# Codeshelf-0005_v02.net
KiCad netlist of a schematic drawn in EAGLE
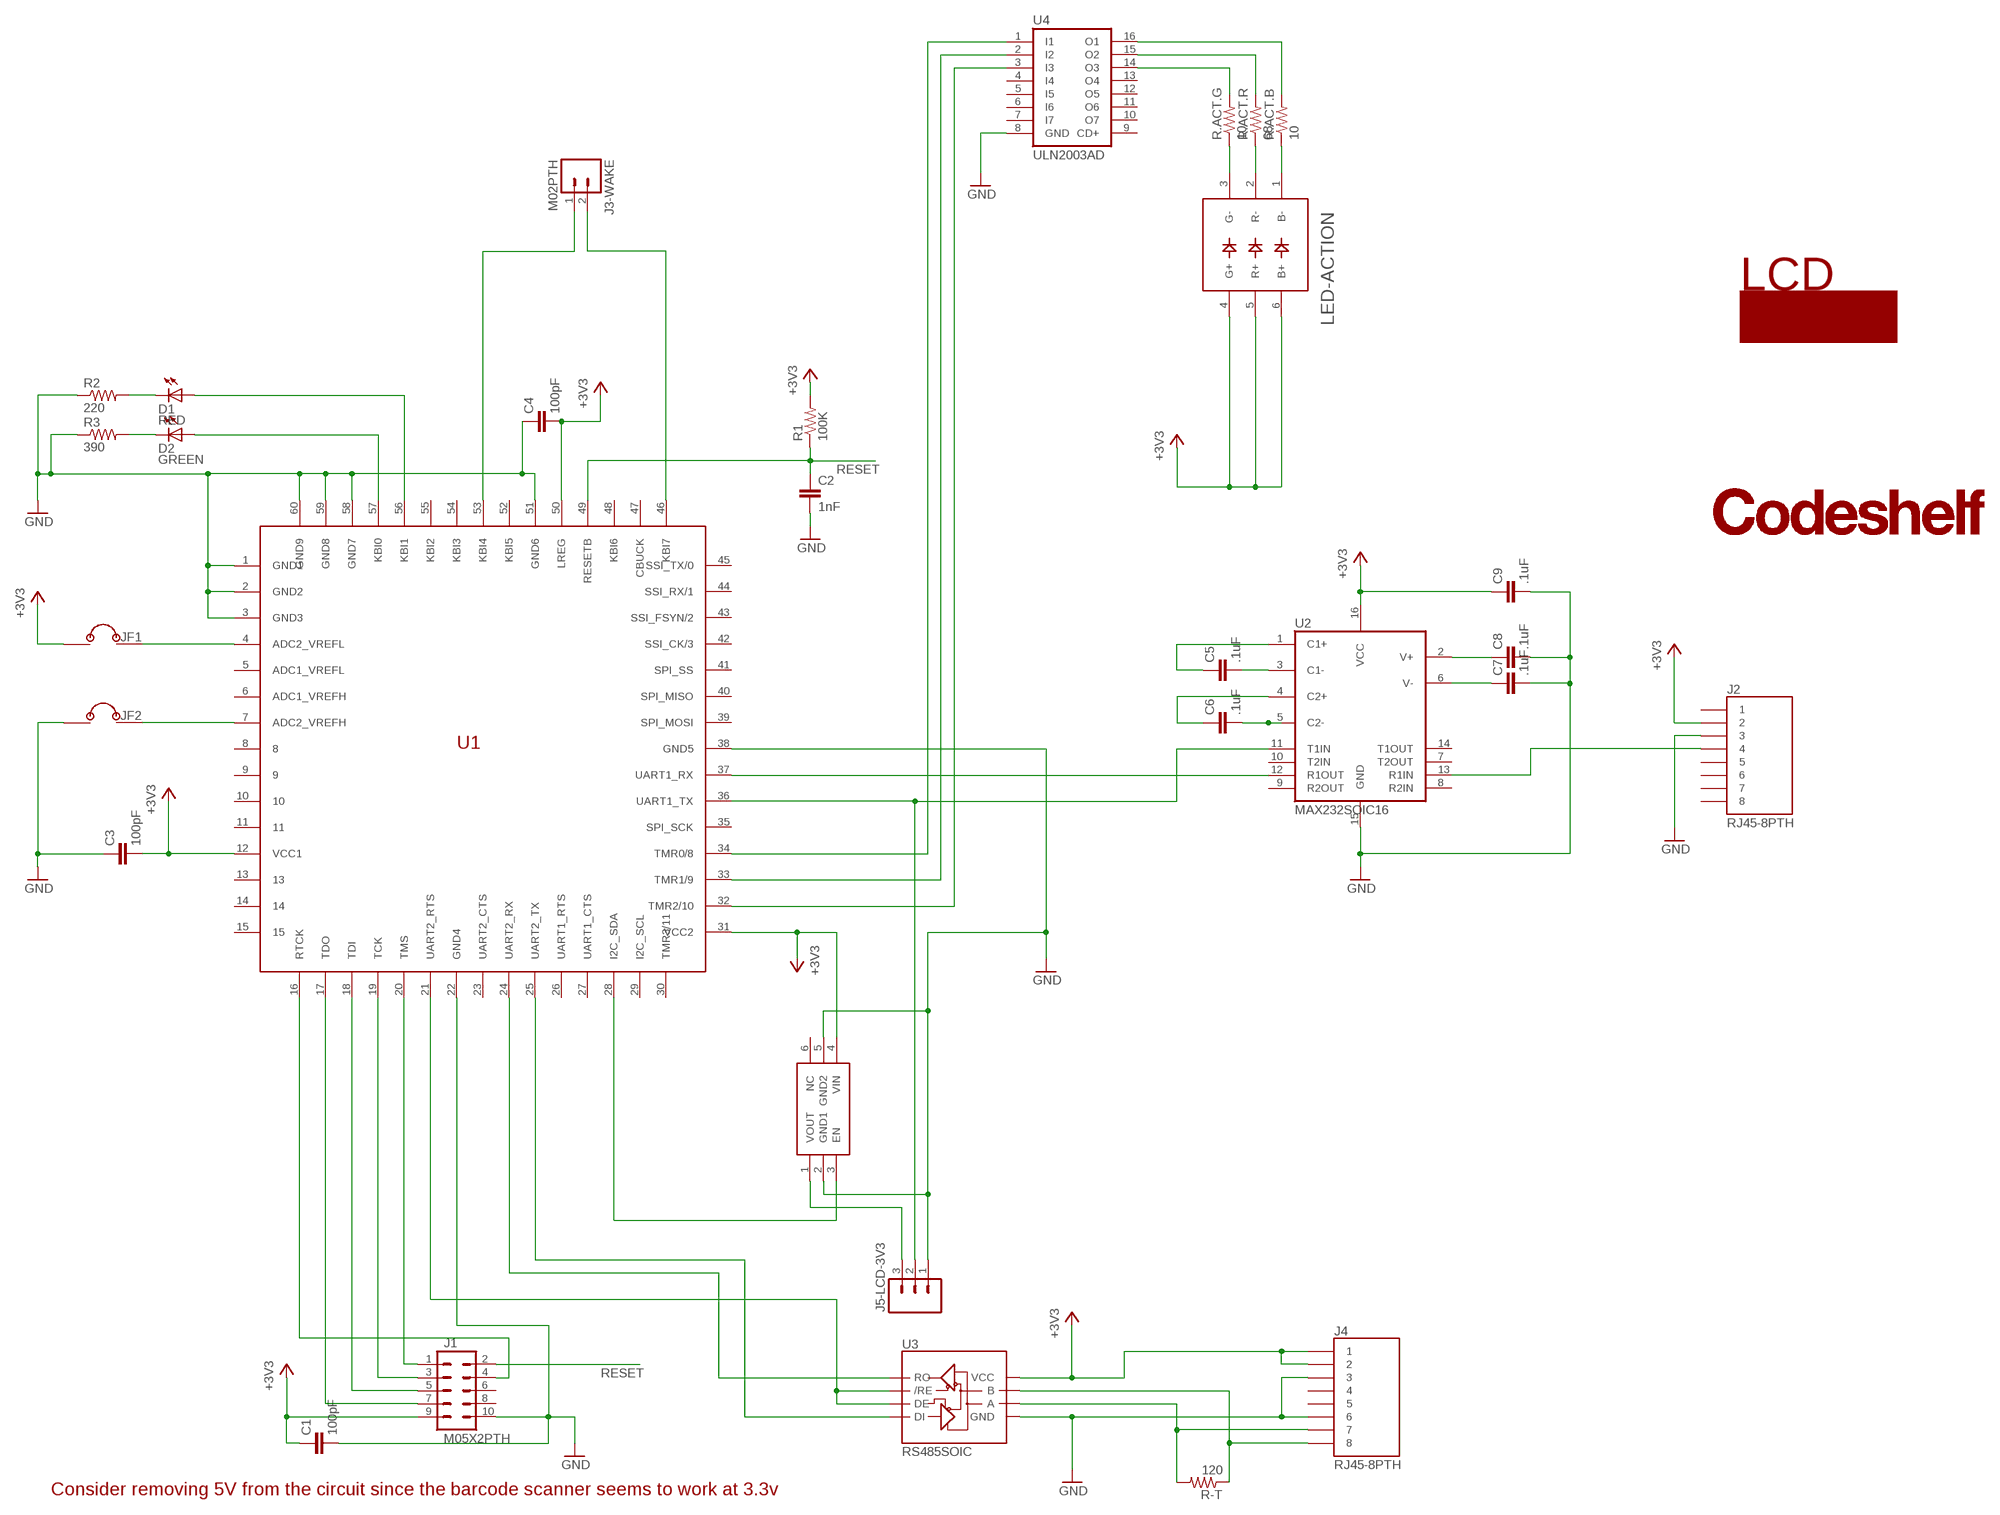
[diagram p0: schematic, sheet 1]
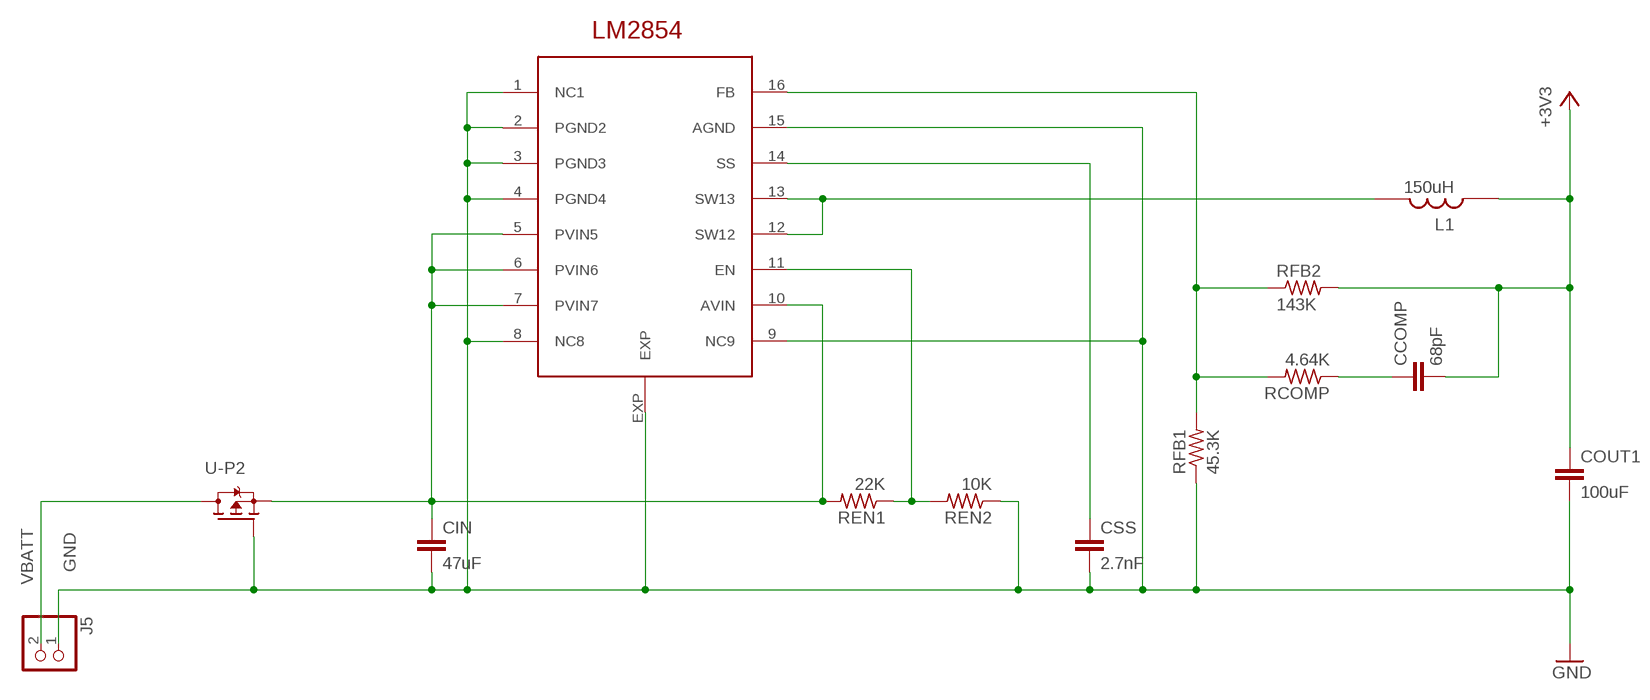
[diagram p1: schematic, sheet 2]

(export (version "E")
  (design (tool "Eeschema 10.0.6"))
  (components
    (comp (ref "C1")
      (value "100pF")
      (footprint "eagle-import:C0603")
      (libsource (lib "eagle-import") (part "RF-C0603"))
    )
    (comp (ref "C2")
      (value "1nF")
      (footprint "eagle-import:C0603")
      (libsource (lib "eagle-import") (part "RF-C0603"))
    )
    (comp (ref "C3")
      (value "100pF")
      (footprint "eagle-import:C0603")
      (libsource (lib "eagle-import") (part "RF-C0603"))
    )
    (comp (ref "C4")
      (value "100pF")
      (footprint "eagle-import:C0603")
      (libsource (lib "eagle-import") (part "RF-C0603"))
    )
    (comp (ref "C5")
      (value ".1uF")
      (footprint "eagle-import:C0402")
      (libsource (lib "eagle-import") (part "RF-C0402"))
    )
    (comp (ref "C6")
      (value ".1uF")
      (footprint "eagle-import:C0402")
      (libsource (lib "eagle-import") (part "RF-C0402"))
    )
    (comp (ref "C7")
      (value ".1uF")
      (footprint "eagle-import:C0402")
      (libsource (lib "eagle-import") (part "RF-C0402"))
    )
    (comp (ref "C8")
      (value ".1uF")
      (footprint "eagle-import:C0402")
      (libsource (lib "eagle-import") (part "RF-C0402"))
    )
    (comp (ref "C9")
      (value ".1uF")
      (footprint "eagle-import:C0402")
      (libsource (lib "eagle-import") (part "RF-C0402"))
    )
    (comp (ref "D1")
      (value "RED")
      (footprint "eagle-import:CHIP-LED0805")
      (libsource (lib "eagle-import") (part "LEDCHIP-LED0805"))
    )
    (comp (ref "D2")
      (value "GREEN")
      (footprint "eagle-import:CHIP-LED0805")
      (libsource (lib "eagle-import") (part "LEDCHIP-LED0805"))
    )
    (comp (ref "J1")
      (value "M05X2PTH")
      (footprint "eagle-import:AVR_ICSP")
      (libsource (lib "eagle-import") (part "M05X2PTH"))
    )
    (comp (ref "J2")
      (value "RJ45-8PTH")
      (footprint "eagle-import:RJ45-8")
      (libsource (lib "eagle-import") (part "RJ45-8PTH"))
    )
    (comp (ref "J3-WAKE")
      (value "M02PTH")
      (footprint "eagle-import:1X02")
      (libsource (lib "eagle-import") (part "M02PTH"))
    )
    (comp (ref "J4")
      (value "RJ45-8PTH")
      (footprint "eagle-import:RJ45-8")
      (libsource (lib "eagle-import") (part "RJ45-8PTH"))
    )
    (comp (ref "J5-LCD-3V3")
      (value "M03PTH")
      (footprint "eagle-import:1X03")
      (libsource (lib "eagle-import") (part "M03PTH"))
    )
    (comp (ref "JF1")
      (value "JUMPER-2X-SMT-VIA")
      (footprint "eagle-import:JUMPER-VIA-2X")
      (libsource (lib "eagle-import") (part "JUMPER-2X-SMT-VIA"))
    )
    (comp (ref "JF2")
      (value "JUMPER-2X-SMT-VIA")
      (footprint "eagle-import:JUMPER-VIA-2X")
      (libsource (lib "eagle-import") (part "JUMPER-2X-SMT-VIA"))
    )
    (comp (ref "LCD")
      (value "LCD-SPARKFUN")
      (footprint "eagle-import:LCD-20X4-SPARKFUN")
      (libsource (lib "eagle-import") (part "LCD-SPARKFUN20X4"))
    )
    (comp (ref "LED-ACTION")
      (value "LED5060A")
      (footprint "eagle-import:PLCC-6")
      (libsource (lib "eagle-import") (part "LED5060A"))
    )
    (comp (ref "LOGO")
      (value "CODESHELF-LOGO")
      (footprint "eagle-import:CODESHELF-LOGO")
      (libsource (lib "eagle-import") (part "CODESHELF-LOGO"))
    )
    (comp (ref "R-T")
      (value "120")
      (footprint "eagle-import:RF-R0402")
      (libsource (lib "eagle-import") (part "RF-R0402"))
    )
    (comp (ref "R.ACT.B")
      (value "10")
      (footprint "eagle-import:RF-R0402")
      (libsource (lib "eagle-import") (part "RF-R0402"))
    )
    (comp (ref "R.ACT.G")
      (value "10")
      (footprint "eagle-import:RF-R0402")
      (libsource (lib "eagle-import") (part "RF-R0402"))
    )
    (comp (ref "R.ACT.R")
      (value "68")
      (footprint "eagle-import:RF-R0402")
      (libsource (lib "eagle-import") (part "RF-R0402"))
    )
    (comp (ref "R1")
      (value "100K")
      (footprint "eagle-import:RF-R0402")
      (libsource (lib "eagle-import") (part "RF-R0402"))
    )
    (comp (ref "R2")
      (value "220")
      (footprint "eagle-import:RF-R0402")
      (libsource (lib "eagle-import") (part "RF-R0402"))
    )
    (comp (ref "R3")
      (value "390")
      (footprint "eagle-import:RF-R0402")
      (libsource (lib "eagle-import") (part "RF-R0402"))
    )
    (comp (ref "U1")
      (value "ZSFM201-1A")
      (footprint "eagle-import:ZSFM201-1")
      (libsource (lib "eagle-import") (part "ZSFM201-1A"))
    )
    (comp (ref "U2")
      (value "MAX232SOIC16")
      (footprint "eagle-import:SO016")
      (libsource (lib "eagle-import") (part "MAX232SOIC16"))
    )
    (comp (ref "U3")
      (value "RS485SOIC")
      (footprint "eagle-import:SO08")
      (libsource (lib "eagle-import") (part "RS485SOIC"))
    )
    (comp (ref "U4")
      (value "ULN2003AD")
      (footprint "eagle-import:SO16")
      (libsource (lib "eagle-import") (part "ULN2003AD"))
    )
    (comp (ref "U6")
      (value "MIC94061C6")
      (footprint "eagle-import:SC70-6L")
      (libsource (lib "eagle-import") (part "MIC94061C6"))
    )
    (comp (ref "CCOMP")
      (value "68pF")
      (footprint "eagle-import:C0805")
      (libsource (lib "eagle-import") (part "RF-C0805"))
    )
    (comp (ref "CIN")
      (value "47uF")
      (footprint "eagle-import:C1210K")
      (libsource (lib "eagle-import") (part "RF-C1210"))
    )
    (comp (ref "COUT1")
      (value "100uF")
      (footprint "eagle-import:C1210K")
      (libsource (lib "eagle-import") (part "RF-C1210"))
    )
    (comp (ref "CSS")
      (value "2.7nF")
      (footprint "eagle-import:C0805")
      (libsource (lib "eagle-import") (part "RF-C0805"))
    )
    (comp (ref "J5")
      (value "PINHD-1X2/90")
      (footprint "eagle-import:1X02_90")
      (libsource (lib "eagle-import") (part "PINHD-1X2/90"))
    )
    (comp (ref "L1")
      (value "150uH")
      (footprint "eagle-import:SLF10165")
      (libsource (lib "eagle-import") (part "INDUCTOR-SMD-UNUSUAL-SLF10165"))
    )
    (comp (ref "RCOMP")
      (value "4.64K")
      (footprint "eagle-import:RF-R0402")
      (libsource (lib "eagle-import") (part "RF-R0402"))
    )
    (comp (ref "REN1")
      (value "22K")
      (footprint "eagle-import:RF-R0402")
      (libsource (lib "eagle-import") (part "RF-R0402"))
    )
    (comp (ref "REN2")
      (value "10K")
      (footprint "eagle-import:RF-R0402")
      (libsource (lib "eagle-import") (part "RF-R0402"))
    )
    (comp (ref "RFB1")
      (value "45.3K")
      (footprint "eagle-import:RF-R0402")
      (libsource (lib "eagle-import") (part "RF-R0402"))
    )
    (comp (ref "RFB2")
      (value "143K")
      (footprint "eagle-import:RF-R0402")
      (libsource (lib "eagle-import") (part "RF-R0402"))
    )
    (comp (ref "U-P1")
      (value "LM2854MH")
      (footprint "eagle-import:HTSSOP16PWP")
      (libsource (lib "eagle-import") (part "LM2854MH"))
    )
    (comp (ref "U-P2")
      (value "PCHANNEL-MOSFET-DPAK")
      (footprint "eagle-import:DPAK")
      (libsource (lib "eagle-import") (part "PCHANNEL-MOSFET-DPAK"))
    )
  )
  (nets
    (net (code "1") (name "+3V3") (class "Default")
      (node (ref "C1") (pin "1") (pinfunction "1_1") (pintype "passive"))
      (node (ref "C3") (pin "2") (pinfunction "2_2") (pintype "passive"))
      (node (ref "C4") (pin "2") (pinfunction "2_2") (pintype "passive"))
      (node (ref "C9") (pin "1") (pinfunction "1_1") (pintype "passive"))
      (node (ref "CCOMP") (pin "2") (pinfunction "2_2") (pintype "passive"))
      (node (ref "COUT1") (pin "1") (pinfunction "1_1") (pintype "passive"))
      (node (ref "J1") (pin "9") (pinfunction "9_9") (pintype "passive"))
      (node (ref "J2") (pin "2") (pinfunction "2_2") (pintype "bidirectional"))
      (node (ref "J4") (pin "1") (pinfunction "1_1") (pintype "bidirectional"))
      (node (ref "J4") (pin "2") (pinfunction "2_2") (pintype "bidirectional"))
      (node (ref "JF1") (pin "1") (pinfunction "1_1") (pintype "bidirectional"))
      (node (ref "L1") (pin "2") (pinfunction "2_2") (pintype "bidirectional"))
      (node (ref "LED-ACTION") (pin "4") (pinfunction "G+_4") (pintype "bidirectional"))
      (node (ref "LED-ACTION") (pin "5") (pinfunction "R+_5") (pintype "bidirectional"))
      (node (ref "LED-ACTION") (pin "6") (pinfunction "B+_6") (pintype "bidirectional"))
      (node (ref "R1") (pin "2") (pinfunction "2_2") (pintype "passive"))
      (node (ref "RFB2") (pin "2") (pinfunction "2_2") (pintype "passive"))
      (node (ref "U1") (pin "12") (pinfunction "VCC1_12") (pintype "power_in"))
      (node (ref "U1") (pin "31") (pinfunction "VCC2_31") (pintype "power_in"))
      (node (ref "U1") (pin "50") (pinfunction "LREG_50") (pintype "bidirectional"))
      (node (ref "U2") (pin "16") (pinfunction "VCC_16") (pintype "bidirectional"))
      (node (ref "U3") (pin "8") (pinfunction "VCC_8") (pintype "bidirectional"))
      (node (ref "U6") (pin "4") (pinfunction "VIN_4") (pintype "bidirectional"))
    )
    (net (code "2") (name "GND") (class "Default")
      (node (ref "C1") (pin "2") (pinfunction "2_2") (pintype "passive"))
      (node (ref "C2") (pin "2") (pinfunction "2_2") (pintype "passive"))
      (node (ref "C3") (pin "1") (pinfunction "1_1") (pintype "passive"))
      (node (ref "C4") (pin "1") (pinfunction "1_1") (pintype "passive"))
      (node (ref "C7") (pin "2") (pinfunction "2_2") (pintype "passive"))
      (node (ref "C8") (pin "2") (pinfunction "2_2") (pintype "passive"))
      (node (ref "C9") (pin "2") (pinfunction "2_2") (pintype "passive"))
      (node (ref "CIN") (pin "2") (pinfunction "2_2") (pintype "passive"))
      (node (ref "COUT1") (pin "2") (pinfunction "2_2") (pintype "passive"))
      (node (ref "CSS") (pin "2") (pinfunction "2_2") (pintype "passive"))
      (node (ref "J1") (pin "10") (pinfunction "10_10") (pintype "passive"))
      (node (ref "J2") (pin "3") (pinfunction "3_3") (pintype "bidirectional"))
      (node (ref "J4") (pin "3") (pinfunction "3_3") (pintype "bidirectional"))
      (node (ref "J4") (pin "6") (pinfunction "6_6") (pintype "bidirectional"))
      (node (ref "J5") (pin "1") (pinfunction "1_1") (pintype "passive"))
      (node (ref "J5-LCD-3V3") (pin "1") (pinfunction "1_1") (pintype "passive"))
      (node (ref "JF2") (pin "1") (pinfunction "1_1") (pintype "bidirectional"))
      (node (ref "R2") (pin "1") (pinfunction "1_1") (pintype "passive"))
      (node (ref "R3") (pin "1") (pinfunction "1_1") (pintype "passive"))
      (node (ref "REN2") (pin "1") (pinfunction "1_1") (pintype "passive"))
      (node (ref "RFB1") (pin "1") (pinfunction "1_1") (pintype "passive"))
      (node (ref "U-P1") (pin "1") (pinfunction "NC1_1") (pintype "bidirectional"))
      (node (ref "U-P1") (pin "15") (pinfunction "AGND_15") (pintype "bidirectional"))
      (node (ref "U-P1") (pin "2") (pinfunction "PGND2_2") (pintype "bidirectional"))
      (node (ref "U-P1") (pin "3") (pinfunction "PGND3_3") (pintype "bidirectional"))
      (node (ref "U-P1") (pin "4") (pinfunction "PGND4_4") (pintype "bidirectional"))
      (node (ref "U-P1") (pin "8") (pinfunction "NC8_8") (pintype "bidirectional"))
      (node (ref "U-P1") (pin "9") (pinfunction "NC9_9") (pintype "bidirectional"))
      (node (ref "U-P1") (pin "EXP") (pinfunction "EXP_EXP") (pintype "bidirectional"))
      (node (ref "U-P2") (pin "1") (pinfunction "G_1") (pintype "passive"))
      (node (ref "U1") (pin "1") (pinfunction "GND1_1") (pintype "power_in"))
      (node (ref "U1") (pin "2") (pinfunction "GND2_2") (pintype "power_in"))
      (node (ref "U1") (pin "22") (pinfunction "GND4_22") (pintype "power_in"))
      (node (ref "U1") (pin "3") (pinfunction "GND3_3") (pintype "power_in"))
      (node (ref "U1") (pin "38") (pinfunction "GND5_38") (pintype "power_in"))
      (node (ref "U1") (pin "51") (pinfunction "GND6_51") (pintype "power_in"))
      (node (ref "U1") (pin "58") (pinfunction "GND7_58") (pintype "power_in"))
      (node (ref "U1") (pin "59") (pinfunction "GND8_59") (pintype "power_in"))
      (node (ref "U1") (pin "60") (pinfunction "GND9_60") (pintype "power_in"))
      (node (ref "U2") (pin "15") (pinfunction "GND_15") (pintype "bidirectional"))
      (node (ref "U3") (pin "5") (pinfunction "GND_5") (pintype "bidirectional"))
      (node (ref "U4") (pin "8") (pinfunction "GND_8") (pintype "power_in"))
      (node (ref "U6") (pin "2") (pinfunction "GND1_2") (pintype "bidirectional"))
      (node (ref "U6") (pin "5") (pinfunction "GND2_5") (pintype "bidirectional"))
    )
    (net (code "3") (name "Net-(CCOMP-Pad1)") (class "Default")
      (node (ref "CCOMP") (pin "1") (pinfunction "1_1") (pintype "passive"))
      (node (ref "RCOMP") (pin "1") (pinfunction "1_1") (pintype "passive"))
    )
    (net (code "4") (name "Net-(D1-PadC)") (class "Default")
      (node (ref "D1") (pin "C") (pinfunction "C_C") (pintype "passive"))
      (node (ref "R2") (pin "2") (pinfunction "2_2") (pintype "passive"))
    )
    (net (code "5") (name "Net-(D2-PadC)") (class "Default")
      (node (ref "D2") (pin "C") (pinfunction "C_C") (pintype "passive"))
      (node (ref "R3") (pin "2") (pinfunction "2_2") (pintype "passive"))
    )
    (net (code "6") (name "Net-(LED-ACTION-B-)") (class "Default")
      (node (ref "LED-ACTION") (pin "1") (pinfunction "B-_1") (pintype "bidirectional"))
      (node (ref "R.ACT.B") (pin "1") (pinfunction "1_1") (pintype "passive"))
    )
    (net (code "7") (name "Net-(LED-ACTION-G-)") (class "Default")
      (node (ref "LED-ACTION") (pin "3") (pinfunction "G-_3") (pintype "bidirectional"))
      (node (ref "R.ACT.G") (pin "1") (pinfunction "1_1") (pintype "passive"))
    )
    (net (code "8") (name "Net-(LED-ACTION-R-)") (class "Default")
      (node (ref "LED-ACTION") (pin "2") (pinfunction "R-_2") (pintype "bidirectional"))
      (node (ref "R.ACT.R") (pin "1") (pinfunction "1_1") (pintype "passive"))
    )
    (net (code "9") (name "Net-(U-P1-AVIN)") (class "Default")
      (node (ref "CIN") (pin "1") (pinfunction "1_1") (pintype "passive"))
      (node (ref "REN1") (pin "2") (pinfunction "2_2") (pintype "passive"))
      (node (ref "U-P1") (pin "10") (pinfunction "AVIN_10") (pintype "bidirectional"))
      (node (ref "U-P1") (pin "5") (pinfunction "PVIN5_5") (pintype "bidirectional"))
      (node (ref "U-P1") (pin "6") (pinfunction "PVIN6_6") (pintype "bidirectional"))
      (node (ref "U-P1") (pin "7") (pinfunction "PVIN7_7") (pintype "bidirectional"))
      (node (ref "U-P2") (pin "3") (pinfunction "S_3") (pintype "passive"))
    )
    (net (code "10") (name "Net-(U-P1-EN)") (class "Default")
      (node (ref "REN1") (pin "1") (pinfunction "1_1") (pintype "passive"))
      (node (ref "REN2") (pin "2") (pinfunction "2_2") (pintype "passive"))
      (node (ref "U-P1") (pin "11") (pinfunction "EN_11") (pintype "bidirectional"))
    )
    (net (code "11") (name "Net-(U-P1-FB)") (class "Default")
      (node (ref "RCOMP") (pin "2") (pinfunction "2_2") (pintype "passive"))
      (node (ref "RFB1") (pin "2") (pinfunction "2_2") (pintype "passive"))
      (node (ref "RFB2") (pin "1") (pinfunction "1_1") (pintype "passive"))
      (node (ref "U-P1") (pin "16") (pinfunction "FB_16") (pintype "bidirectional"))
    )
    (net (code "12") (name "Net-(U-P1-SS)") (class "Default")
      (node (ref "CSS") (pin "1") (pinfunction "1_1") (pintype "passive"))
      (node (ref "U-P1") (pin "14") (pinfunction "SS_14") (pintype "bidirectional"))
    )
    (net (code "13") (name "Net-(U-P1-SW12)") (class "Default")
      (node (ref "L1") (pin "1") (pinfunction "1_1") (pintype "bidirectional"))
      (node (ref "U-P1") (pin "12") (pinfunction "SW12_12") (pintype "bidirectional"))
      (node (ref "U-P1") (pin "13") (pinfunction "SW13_13") (pintype "bidirectional"))
    )
    (net (code "14") (name "Net-(U1-ADC2_VREFH)") (class "Default")
      (node (ref "JF2") (pin "2") (pinfunction "2_2") (pintype "bidirectional"))
      (node (ref "U1") (pin "7") (pinfunction "ADC2_VREFH_7") (pintype "bidirectional"))
    )
    (net (code "15") (name "Net-(U1-ADC2_VREFL)") (class "Default")
      (node (ref "JF1") (pin "2") (pinfunction "2_2") (pintype "bidirectional"))
      (node (ref "U1") (pin "4") (pinfunction "ADC2_VREFL_4") (pintype "bidirectional"))
    )
    (net (code "16") (name "Net-(U1-I2C_SDA)") (class "Default")
      (node (ref "U1") (pin "28") (pinfunction "I2C_SDA_28") (pintype "bidirectional"))
      (node (ref "U6") (pin "3") (pinfunction "EN_3") (pintype "bidirectional"))
    )
    (net (code "17") (name "Net-(U1-KBI0)") (class "Default")
      (node (ref "D2") (pin "A") (pinfunction "A_A") (pintype "passive"))
      (node (ref "U1") (pin "57") (pinfunction "KBI0_57") (pintype "bidirectional"))
    )
    (net (code "18") (name "Net-(U1-KBI1)") (class "Default")
      (node (ref "D1") (pin "A") (pinfunction "A_A") (pintype "passive"))
      (node (ref "U1") (pin "56") (pinfunction "KBI1_56") (pintype "bidirectional"))
    )
    (net (code "19") (name "Net-(U1-KBI4)") (class "Default")
      (node (ref "J3-WAKE") (pin "1") (pinfunction "1_1") (pintype "passive"))
      (node (ref "U1") (pin "53") (pinfunction "KBI4_53") (pintype "bidirectional"))
    )
    (net (code "20") (name "Net-(U1-KBI7)") (class "Default")
      (node (ref "J3-WAKE") (pin "2") (pinfunction "2_2") (pintype "passive"))
      (node (ref "U1") (pin "46") (pinfunction "KBI7_46") (pintype "bidirectional"))
    )
    (net (code "21") (name "Net-(U1-RTCK)") (class "Default")
      (node (ref "J1") (pin "4") (pinfunction "4_4") (pintype "passive"))
      (node (ref "U1") (pin "16") (pinfunction "RTCK_16") (pintype "bidirectional"))
    )
    (net (code "22") (name "Net-(U1-TCK)") (class "Default")
      (node (ref "J1") (pin "3") (pinfunction "3_3") (pintype "passive"))
      (node (ref "U1") (pin "19") (pinfunction "TCK_19") (pintype "bidirectional"))
    )
    (net (code "23") (name "Net-(U1-TDI)") (class "Default")
      (node (ref "J1") (pin "5") (pinfunction "5_5") (pintype "passive"))
      (node (ref "U1") (pin "18") (pinfunction "TDI_18") (pintype "bidirectional"))
    )
    (net (code "24") (name "Net-(U1-TDO)") (class "Default")
      (node (ref "J1") (pin "7") (pinfunction "7_7") (pintype "passive"))
      (node (ref "U1") (pin "17") (pinfunction "TDO_17") (pintype "bidirectional"))
    )
    (net (code "25") (name "Net-(U1-TMR0{slash}8)") (class "Default")
      (node (ref "U1") (pin "34") (pinfunction "TMR0/8_34") (pintype "bidirectional"))
      (node (ref "U4") (pin "1") (pinfunction "I1_1") (pintype "input"))
    )
    (net (code "26") (name "Net-(U1-TMR1{slash}9)") (class "Default")
      (node (ref "U1") (pin "33") (pinfunction "TMR1/9_33") (pintype "bidirectional"))
      (node (ref "U4") (pin "2") (pinfunction "I2_2") (pintype "input"))
    )
    (net (code "27") (name "Net-(U1-TMR2{slash}10)") (class "Default")
      (node (ref "U1") (pin "32") (pinfunction "TMR2/10_32") (pintype "bidirectional"))
      (node (ref "U4") (pin "3") (pinfunction "I3_3") (pintype "input"))
    )
    (net (code "28") (name "Net-(U1-TMS)") (class "Default")
      (node (ref "J1") (pin "1") (pinfunction "1_1") (pintype "passive"))
      (node (ref "U1") (pin "20") (pinfunction "TMS_20") (pintype "bidirectional"))
    )
    (net (code "29") (name "Net-(U1-UART1_RX)") (class "Default")
      (node (ref "U1") (pin "37") (pinfunction "UART1_RX_37") (pintype "bidirectional"))
      (node (ref "U2") (pin "12") (pinfunction "R1OUT_12") (pintype "output"))
    )
    (net (code "30") (name "Net-(U1-UART1_TX)") (class "Default")
      (node (ref "J5-LCD-3V3") (pin "2") (pinfunction "2_2") (pintype "passive"))
      (node (ref "U1") (pin "36") (pinfunction "UART1_TX_36") (pintype "bidirectional"))
      (node (ref "U2") (pin "11") (pinfunction "T1IN_11") (pintype "input"))
    )
    (net (code "31") (name "Net-(U1-UART2_RTS)") (class "Default")
      (node (ref "U1") (pin "21") (pinfunction "UART2_RTS_21") (pintype "bidirectional"))
      (node (ref "U3") (pin "2") (pinfunction "/RE_2") (pintype "bidirectional"))
      (node (ref "U3") (pin "3") (pinfunction "DE_3") (pintype "bidirectional"))
    )
    (net (code "32") (name "Net-(U1-UART2_RX)") (class "Default")
      (node (ref "U1") (pin "24") (pinfunction "UART2_RX_24") (pintype "bidirectional"))
      (node (ref "U3") (pin "1") (pinfunction "RO_1") (pintype "bidirectional"))
    )
    (net (code "33") (name "Net-(U1-UART2_TX)") (class "Default")
      (node (ref "U1") (pin "25") (pinfunction "UART2_TX_25") (pintype "bidirectional"))
      (node (ref "U3") (pin "4") (pinfunction "DI_4") (pintype "bidirectional"))
    )
    (net (code "34") (name "Net-(U2-C1+)") (class "Default")
      (node (ref "C5") (pin "1") (pinfunction "1_1") (pintype "passive"))
      (node (ref "U2") (pin "1") (pinfunction "C1+_1") (pintype "bidirectional"))
    )
    (net (code "35") (name "Net-(U2-C1-)") (class "Default")
      (node (ref "C5") (pin "2") (pinfunction "2_2") (pintype "passive"))
      (node (ref "U2") (pin "3") (pinfunction "C1-_3") (pintype "bidirectional"))
    )
    (net (code "36") (name "Net-(U2-C2+)") (class "Default")
      (node (ref "C6") (pin "1") (pinfunction "1_1") (pintype "passive"))
      (node (ref "U2") (pin "4") (pinfunction "C2+_4") (pintype "bidirectional"))
    )
    (net (code "37") (name "Net-(U2-C2-)") (class "Default")
      (node (ref "C6") (pin "2") (pinfunction "2_2") (pintype "passive"))
      (node (ref "U2") (pin "5") (pinfunction "C2-_5") (pintype "bidirectional"))
    )
    (net (code "38") (name "Net-(U2-R1IN)") (class "Default")
      (node (ref "J2") (pin "4") (pinfunction "4_4") (pintype "bidirectional"))
      (node (ref "U2") (pin "13") (pinfunction "R1IN_13") (pintype "input"))
    )
    (net (code "39") (name "Net-(U2-V+)") (class "Default")
      (node (ref "C8") (pin "1") (pinfunction "1_1") (pintype "passive"))
      (node (ref "U2") (pin "2") (pinfunction "V+_2") (pintype "bidirectional"))
    )
    (net (code "40") (name "Net-(U2-V-)") (class "Default")
      (node (ref "C7") (pin "1") (pinfunction "1_1") (pintype "passive"))
      (node (ref "U2") (pin "6") (pinfunction "V-_6") (pintype "bidirectional"))
    )
    (net (code "41") (name "Net-(U3-A)") (class "Default")
      (node (ref "J4") (pin "7") (pinfunction "7_7") (pintype "bidirectional"))
      (node (ref "R-T") (pin "2") (pinfunction "2_2") (pintype "passive"))
      (node (ref "U3") (pin "6") (pinfunction "A_6") (pintype "bidirectional"))
    )
    (net (code "42") (name "Net-(U3-B)") (class "Default")
      (node (ref "J4") (pin "8") (pinfunction "8_8") (pintype "bidirectional"))
      (node (ref "R-T") (pin "1") (pinfunction "1_1") (pintype "passive"))
      (node (ref "U3") (pin "7") (pinfunction "B_7") (pintype "bidirectional"))
    )
    (net (code "43") (name "Net-(U4-O1)") (class "Default")
      (node (ref "R.ACT.B") (pin "2") (pinfunction "2_2") (pintype "passive"))
      (node (ref "U4") (pin "16") (pinfunction "O1_16") (pintype "open_collector"))
    )
    (net (code "44") (name "Net-(U4-O2)") (class "Default")
      (node (ref "R.ACT.R") (pin "2") (pinfunction "2_2") (pintype "passive"))
      (node (ref "U4") (pin "15") (pinfunction "O2_15") (pintype "open_collector"))
    )
    (net (code "45") (name "Net-(U4-O3)") (class "Default")
      (node (ref "R.ACT.G") (pin "2") (pinfunction "2_2") (pintype "passive"))
      (node (ref "U4") (pin "14") (pinfunction "O3_14") (pintype "open_collector"))
    )
    (net (code "46") (name "Net-(U6-VOUT)") (class "Default")
      (node (ref "J5-LCD-3V3") (pin "3") (pinfunction "3_3") (pintype "passive"))
      (node (ref "U6") (pin "1") (pinfunction "VOUT_1") (pintype "bidirectional"))
    )
    (net (code "47") (name "RESET") (class "Default")
      (node (ref "C2") (pin "1") (pinfunction "1_1") (pintype "passive"))
      (node (ref "J1") (pin "2") (pinfunction "2_2") (pintype "passive"))
      (node (ref "R1") (pin "1") (pinfunction "1_1") (pintype "passive"))
      (node (ref "U1") (pin "49") (pinfunction "RESETB_49") (pintype "bidirectional"))
    )
    (net (code "48") (name "VBATT") (class "Default")
      (node (ref "J5") (pin "2") (pinfunction "2_2") (pintype "passive"))
      (node (ref "U-P2") (pin "4") (pinfunction "D_4") (pintype "passive"))
    )
    (net (code "49") (name "unconnected-(J1-Pad6)") (class "Default")
      (node (ref "J1") (pin "6") (pinfunction "6_6") (pintype "passive"))
    )
    (net (code "50") (name "unconnected-(J1-Pad8)") (class "Default")
      (node (ref "J1") (pin "8") (pinfunction "8_8") (pintype "passive"))
    )
    (net (code "51") (name "unconnected-(J2-Pad1)") (class "Default")
      (node (ref "J2") (pin "1") (pinfunction "1_1") (pintype "bidirectional"))
    )
    (net (code "52") (name "unconnected-(J2-Pad5)") (class "Default")
      (node (ref "J2") (pin "5") (pinfunction "5_5") (pintype "bidirectional"))
    )
    (net (code "53") (name "unconnected-(J2-Pad6)") (class "Default")
      (node (ref "J2") (pin "6") (pinfunction "6_6") (pintype "bidirectional"))
    )
    (net (code "54") (name "unconnected-(J2-Pad7)") (class "Default")
      (node (ref "J2") (pin "7") (pinfunction "7_7") (pintype "bidirectional"))
    )
    (net (code "55") (name "unconnected-(J2-Pad8)") (class "Default")
      (node (ref "J2") (pin "8") (pinfunction "8_8") (pintype "bidirectional"))
    )
    (net (code "56") (name "unconnected-(J4-Pad4)") (class "Default")
      (node (ref "J4") (pin "4") (pinfunction "4_4") (pintype "bidirectional"))
    )
    (net (code "57") (name "unconnected-(J4-Pad5)") (class "Default")
      (node (ref "J4") (pin "5") (pinfunction "5_5") (pintype "bidirectional"))
    )
    (net (code "58") (name "unconnected-(U1-ADC1_VREFH-Pad6)") (class "Default")
      (node (ref "U1") (pin "6") (pinfunction "ADC1_VREFH_6") (pintype "bidirectional"))
    )
    (net (code "59") (name "unconnected-(U1-ADC1_VREFL-Pad5)") (class "Default")
      (node (ref "U1") (pin "5") (pinfunction "ADC1_VREFL_5") (pintype "bidirectional"))
    )
    (net (code "60") (name "unconnected-(U1-CBUCK-Pad47)") (class "Default")
      (node (ref "U1") (pin "47") (pinfunction "CBUCK_47") (pintype "bidirectional"))
    )
    (net (code "61") (name "unconnected-(U1-I2C_SCL-Pad29)") (class "Default")
      (node (ref "U1") (pin "29") (pinfunction "I2C_SCL_29") (pintype "bidirectional"))
    )
    (net (code "62") (name "unconnected-(U1-KBI2-Pad55)") (class "Default")
      (node (ref "U1") (pin "55") (pinfunction "KBI2_55") (pintype "bidirectional"))
    )
    (net (code "63") (name "unconnected-(U1-KBI3-Pad54)") (class "Default")
      (node (ref "U1") (pin "54") (pinfunction "KBI3_54") (pintype "bidirectional"))
    )
    (net (code "64") (name "unconnected-(U1-KBI5-Pad52)") (class "Default")
      (node (ref "U1") (pin "52") (pinfunction "KBI5_52") (pintype "bidirectional"))
    )
    (net (code "65") (name "unconnected-(U1-KBI6-Pad48)") (class "Default")
      (node (ref "U1") (pin "48") (pinfunction "KBI6_48") (pintype "bidirectional"))
    )
    (net (code "66") (name "unconnected-(U1-Pad8)") (class "Default")
      (node (ref "U1") (pin "8") (pinfunction "8_8") (pintype "bidirectional"))
    )
    (net (code "67") (name "unconnected-(U1-Pad9)") (class "Default")
      (node (ref "U1") (pin "9") (pinfunction "9_9") (pintype "bidirectional"))
    )
    (net (code "68") (name "unconnected-(U1-Pad10)") (class "Default")
      (node (ref "U1") (pin "10") (pinfunction "10_10") (pintype "bidirectional"))
    )
    (net (code "69") (name "unconnected-(U1-Pad11)") (class "Default")
      (node (ref "U1") (pin "11") (pinfunction "11_11") (pintype "bidirectional"))
    )
    (net (code "70") (name "unconnected-(U1-Pad13)") (class "Default")
      (node (ref "U1") (pin "13") (pinfunction "13_13") (pintype "bidirectional"))
    )
    (net (code "71") (name "unconnected-(U1-Pad14)") (class "Default")
      (node (ref "U1") (pin "14") (pinfunction "14_14") (pintype "bidirectional"))
    )
    (net (code "72") (name "unconnected-(U1-Pad15)") (class "Default")
      (node (ref "U1") (pin "15") (pinfunction "15_15") (pintype "bidirectional"))
    )
    (net (code "73") (name "unconnected-(U1-SPI_MISO-Pad40)") (class "Default")
      (node (ref "U1") (pin "40") (pinfunction "SPI_MISO_40") (pintype "bidirectional"))
    )
    (net (code "74") (name "unconnected-(U1-SPI_MOSI-Pad39)") (class "Default")
      (node (ref "U1") (pin "39") (pinfunction "SPI_MOSI_39") (pintype "bidirectional"))
    )
    (net (code "75") (name "unconnected-(U1-SPI_SCK-Pad35)") (class "Default")
      (node (ref "U1") (pin "35") (pinfunction "SPI_SCK_35") (pintype "bidirectional"))
    )
    (net (code "76") (name "unconnected-(U1-SPI_SS-Pad41)") (class "Default")
      (node (ref "U1") (pin "41") (pinfunction "SPI_SS_41") (pintype "bidirectional"))
    )
    (net (code "77") (name "unconnected-(U1-SSI_CK{slash}3-Pad42)") (class "Default")
      (node (ref "U1") (pin "42") (pinfunction "SSI_CK/3_42") (pintype "bidirectional"))
    )
    (net (code "78") (name "unconnected-(U1-SSI_FSYN{slash}2-Pad43)") (class "Default")
      (node (ref "U1") (pin "43") (pinfunction "SSI_FSYN/2_43") (pintype "bidirectional"))
    )
    (net (code "79") (name "unconnected-(U1-SSI_RX{slash}1-Pad44)") (class "Default")
      (node (ref "U1") (pin "44") (pinfunction "SSI_RX/1_44") (pintype "bidirectional"))
    )
    (net (code "80") (name "unconnected-(U1-SSI_TX{slash}0-Pad45)") (class "Default")
      (node (ref "U1") (pin "45") (pinfunction "SSI_TX/0_45") (pintype "bidirectional"))
    )
    (net (code "81") (name "unconnected-(U1-TMR3{slash}11-Pad30)") (class "Default")
      (node (ref "U1") (pin "30") (pinfunction "TMR3/11_30") (pintype "bidirectional"))
    )
    (net (code "82") (name "unconnected-(U1-UART1_CTS-Pad27)") (class "Default")
      (node (ref "U1") (pin "27") (pinfunction "UART1_CTS_27") (pintype "bidirectional"))
    )
    (net (code "83") (name "unconnected-(U1-UART1_RTS-Pad26)") (class "Default")
      (node (ref "U1") (pin "26") (pinfunction "UART1_RTS_26") (pintype "bidirectional"))
    )
    (net (code "84") (name "unconnected-(U1-UART2_CTS-Pad23)") (class "Default")
      (node (ref "U1") (pin "23") (pinfunction "UART2_CTS_23") (pintype "bidirectional"))
    )
    (net (code "85") (name "unconnected-(U2-R2IN-Pad8)") (class "Default")
      (node (ref "U2") (pin "8") (pinfunction "R2IN_8") (pintype "input"))
    )
    (net (code "86") (name "unconnected-(U2-R2OUT-Pad9)") (class "Default")
      (node (ref "U2") (pin "9") (pinfunction "R2OUT_9") (pintype "output"))
    )
    (net (code "87") (name "unconnected-(U2-T1OUT-Pad14)") (class "Default")
      (node (ref "U2") (pin "14") (pinfunction "T1OUT_14") (pintype "output"))
    )
    (net (code "88") (name "unconnected-(U2-T2IN-Pad10)") (class "Default")
      (node (ref "U2") (pin "10") (pinfunction "T2IN_10") (pintype "input"))
    )
    (net (code "89") (name "unconnected-(U2-T2OUT-Pad7)") (class "Default")
      (node (ref "U2") (pin "7") (pinfunction "T2OUT_7") (pintype "output"))
    )
    (net (code "90") (name "unconnected-(U4-CD+-Pad9)") (class "Default")
      (node (ref "U4") (pin "9") (pinfunction "CD+_9") (pintype "passive"))
    )
    (net (code "91") (name "unconnected-(U4-I4-Pad4)") (class "Default")
      (node (ref "U4") (pin "4") (pinfunction "I4_4") (pintype "input"))
    )
    (net (code "92") (name "unconnected-(U4-I5-Pad5)") (class "Default")
      (node (ref "U4") (pin "5") (pinfunction "I5_5") (pintype "input"))
    )
    (net (code "93") (name "unconnected-(U4-I6-Pad6)") (class "Default")
      (node (ref "U4") (pin "6") (pinfunction "I6_6") (pintype "input"))
    )
    (net (code "94") (name "unconnected-(U4-I7-Pad7)") (class "Default")
      (node (ref "U4") (pin "7") (pinfunction "I7_7") (pintype "input"))
    )
    (net (code "95") (name "unconnected-(U4-O4-Pad13)") (class "Default")
      (node (ref "U4") (pin "13") (pinfunction "O4_13") (pintype "open_collector"))
    )
    (net (code "96") (name "unconnected-(U4-O5-Pad12)") (class "Default")
      (node (ref "U4") (pin "12") (pinfunction "O5_12") (pintype "open_collector"))
    )
    (net (code "97") (name "unconnected-(U4-O6-Pad11)") (class "Default")
      (node (ref "U4") (pin "11") (pinfunction "O6_11") (pintype "open_collector"))
    )
    (net (code "98") (name "unconnected-(U4-O7-Pad10)") (class "Default")
      (node (ref "U4") (pin "10") (pinfunction "O7_10") (pintype "open_collector"))
    )
    (net (code "99") (name "unconnected-(U6-NC-Pad6)") (class "Default")
      (node (ref "U6") (pin "6") (pinfunction "NC_6") (pintype "bidirectional"))
    )
  )
)
